# openSX70_ALPHA_V6-2-3-20181104.net
KiCad netlist of a schematic drawn in EAGLE
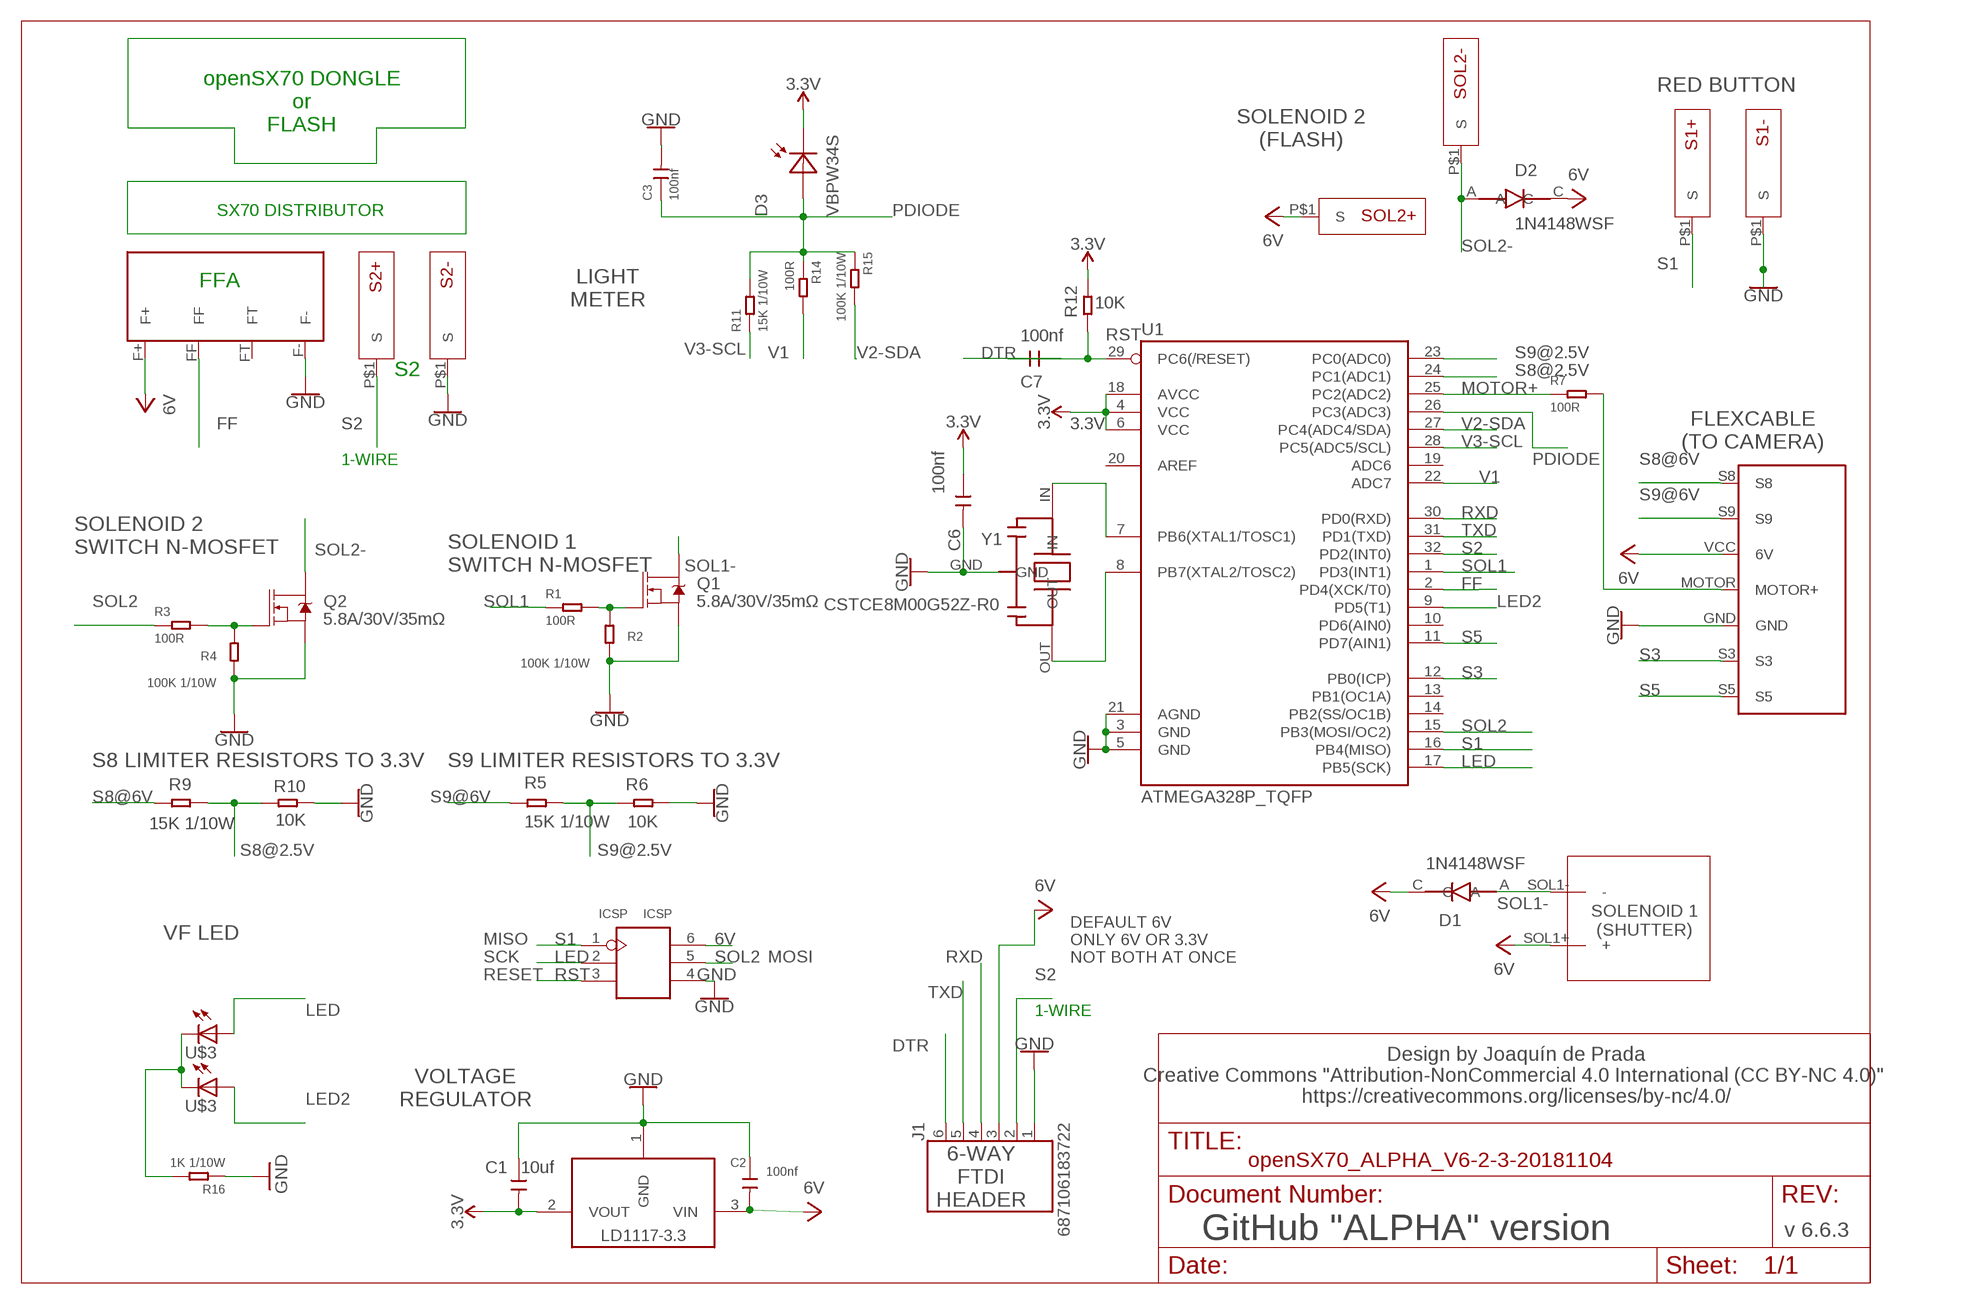
[diagram p0: schematic, sheet 1]

(export (version "E")
  (design (tool "Eeschema 10.0.6"))
  (components
    (comp (ref "C1")
      (value "10uf")
      (footprint "eagle-import:C0603")
      (fields (field (name "MPN") "CC0603KRX5R6BB106"))
      (libsource (lib "eagle-import") (part "CERAMIC-10UF-10V-10%-X5R(0603)"))
    )
    (comp (ref "C2")
      (value "100nf")
      (footprint "eagle-import:C0603")
      (fields (field (name "MPN") "CC0603KRX7R9BB104"))
      (libsource (lib "eagle-import") (part "CERAMIC-100NF-50V-10%-X7R(0603)"))
    )
    (comp (ref "C3")
      (value "100nf")
      (footprint "eagle-import:C0603")
      (fields (field (name "MPN") "CC0603KRX7R9BB104"))
      (libsource (lib "eagle-import") (part "CERAMIC-100NF-50V-10%-X7R(0603)"))
    )
    (comp (ref "C6")
      (value "100nf")
      (footprint "eagle-import:C0603")
      (fields (field (name "MPN") "CC0603KRX7R9BB104"))
      (libsource (lib "eagle-import") (part "CERAMIC-100NF-50V-10%-X7R(0603)"))
    )
    (comp (ref "C7")
      (value "100nf")
      (footprint "eagle-import:C0603")
      (fields (field (name "MPN") "CC0603KRX7R9BB104"))
      (libsource (lib "eagle-import") (part "CERAMIC-100NF-50V-10%-X7R(0603)"))
    )
    (comp (ref "D1")
      (value "1N4148WSF")
      (footprint "eagle-import:SODFL2512X100N")
      (fields (field (name "MANUFACTURER") "Fairchild Semiconductor"))
      (libsource (lib "eagle-import") (part "1N4148WS"))
    )
    (comp (ref "D2")
      (value "1N4148WSF")
      (footprint "eagle-import:SODFL2512X100N")
      (fields (field (name "MANUFACTURER") "Fairchild Semiconductor"))
      (libsource (lib "eagle-import") (part "1N4148WS"))
    )
    (comp (ref "D3")
      (value "VBPW34S")
      (footprint "eagle-import:SOD6439X130N")
      (fields (field (name "DIGI-KEY_PART_NUMBER") "751-1500-1-ND") (field (name "MF") "Vishay"))
      (libsource (lib "eagle-import") (part "VBPW34S"))
    )
    (comp (ref "ICSP")
      (value "ICSP")
      (footprint "eagle-import:H2X3-2.54")
      (libsource (lib "eagle-import") (part "ICSP"))
    )
    (comp (ref "J1")
      (value "687106183722")
      (footprint "eagle-import:687106183722")
      (fields (field (name "MF") "Wurth Electronics"))
      (libsource (lib "eagle-import") (part "687106183722"))
    )
    (comp (ref "LD11172.5V")
      (value "LD1117 2.5V")
      (footprint "eagle-import:SOT223")
      (fields (field (name "MF") "Advanced Monolithic Systems") (field (name "MP") "AMS1117-5.0"))
      (libsource (lib "eagle-import") (part "LD1117-3.3"))
    )
    (comp (ref "Q1")
      (value "5.8A/30V/35mΩ")
      (footprint "eagle-import:SOT23-3")
      (libsource (lib "eagle-import") (part "MOSFET-NCH-AO3404A"))
    )
    (comp (ref "Q2")
      (value "5.8A/30V/35mΩ")
      (footprint "eagle-import:SOT23-3")
      (libsource (lib "eagle-import") (part "MOSFET-NCH-AO3404A"))
    )
    (comp (ref "R1")
      (value "100R")
      (footprint "eagle-import:R0603")
      (fields (field (name "MPN") "RC0603JR-07100RL"))
      (libsource (lib "eagle-import") (part "SMD-RES-100R-5%-1/10W(0603)"))
    )
    (comp (ref "R2")
      (value "100K 1/10W")
      (footprint "eagle-import:R0603")
      (fields (field (name "MPN") "RC0603JR-07100KL"))
      (libsource (lib "eagle-import") (part "SMD-RES-100K-5%-1/10W(0603)"))
    )
    (comp (ref "R3")
      (value "100R")
      (footprint "eagle-import:R0603")
      (fields (field (name "MPN") "RC0603JR-07100RL"))
      (libsource (lib "eagle-import") (part "SMD-RES-100R-5%-1/10W(0603)"))
    )
    (comp (ref "R4")
      (value "100K 1/10W")
      (footprint "eagle-import:R0603")
      (fields (field (name "MPN") "RC0603JR-07100KL"))
      (libsource (lib "eagle-import") (part "SMD-RES-100K-5%-1/10W(0603)"))
    )
    (comp (ref "R5")
      (value "15K 1/10W")
      (footprint "eagle-import:R0603")
      (fields (field (name "MPN") "RC0603FR-0715KL"))
      (libsource (lib "eagle-import") (part "SMD-RES-15K-1%-1/10W(0603)"))
    )
    (comp (ref "R6")
      (value "10K")
      (footprint "eagle-import:R0603")
      (fields (field (name "MPN") "RC0603FR-0710KL"))
      (libsource (lib "eagle-import") (part "SMD-RES-10K-1%-1/10W(0603)"))
    )
    (comp (ref "R7")
      (value "100R")
      (footprint "eagle-import:R0603")
      (fields (field (name "MPN") "RC0603JR-07100RL"))
      (libsource (lib "eagle-import") (part "SMD-RES-100R-5%-1/10W(0603)"))
    )
    (comp (ref "R9")
      (value "15K 1/10W")
      (footprint "eagle-import:R0603")
      (fields (field (name "MPN") "RC0603FR-0715KL"))
      (libsource (lib "eagle-import") (part "SMD-RES-15K-1%-1/10W(0603)"))
    )
    (comp (ref "R10")
      (value "10K")
      (footprint "eagle-import:R0603")
      (fields (field (name "MPN") "RC0603FR-0710KL"))
      (libsource (lib "eagle-import") (part "SMD-RES-10K-1%-1/10W(0603)"))
    )
    (comp (ref "R11")
      (value "15K 1/10W")
      (footprint "eagle-import:R0603")
      (fields (field (name "MPN") "RC0603FR-0715KL"))
      (libsource (lib "eagle-import") (part "SMD-RES-15K-1%-1/10W(0603)"))
    )
    (comp (ref "R12")
      (value "10K")
      (footprint "eagle-import:R0603")
      (fields (field (name "MPN") "RC0603FR-0710KL"))
      (libsource (lib "eagle-import") (part "SMD-RES-10K-1%-1/10W(0603)"))
    )
    (comp (ref "R14")
      (value "100R")
      (footprint "eagle-import:R0603")
      (fields (field (name "MPN") "RC0603JR-07100RL"))
      (libsource (lib "eagle-import") (part "SMD-RES-100R-5%-1/10W(0603)"))
    )
    (comp (ref "R15")
      (value "100K 1/10W")
      (footprint "eagle-import:R0603")
      (fields (field (name "MPN") "RC0603JR-07100KL"))
      (libsource (lib "eagle-import") (part "SMD-RES-100K-5%-1/10W(0603)"))
    )
    (comp (ref "R16")
      (value "1K 1/10W")
      (footprint "eagle-import:R0603")
      (fields (field (name "MPN") "RC0603JR-071KL"))
      (libsource (lib "eagle-import") (part "SMD-RES-1K-5%-1/10W(0603)"))
    )
    (comp (ref "S1+")
      (value "SX70-S-PAD-NEW")
      (footprint "eagle-import:SX70-S-PAD2")
      (libsource (lib "eagle-import") (part "SX70-S-PAD-NEW"))
    )
    (comp (ref "S1-")
      (value "SX70-S-PAD-NEW")
      (footprint "eagle-import:SX70-S-PAD2")
      (libsource (lib "eagle-import") (part "SX70-S-PAD-NEW"))
    )
    (comp (ref "S2+")
      (value "SX70-S-PAD-NEW")
      (footprint "eagle-import:SX70-S-PAD2")
      (libsource (lib "eagle-import") (part "SX70-S-PAD-NEW"))
    )
    (comp (ref "S2-")
      (value "SX70-S-PAD-NEW")
      (footprint "eagle-import:SX70-S-PAD2")
      (libsource (lib "eagle-import") (part "SX70-S-PAD-NEW"))
    )
    (comp (ref "SOL1")
      (value "SX70-SOLENOID1-2PADS")
      (footprint "eagle-import:SX70-SOLENOID1-2")
      (libsource (lib "eagle-import") (part "SX70-SOLENOID1-2PADS"))
    )
    (comp (ref "SOL2+")
      (value "SX70-S-PAD-NEW")
      (footprint "eagle-import:SX70-S-PAD2")
      (libsource (lib "eagle-import") (part "SX70-S-PAD-NEW"))
    )
    (comp (ref "SOL2-")
      (value "SX70-S-PAD-NEW")
      (footprint "eagle-import:SX70-S-PAD2")
      (libsource (lib "eagle-import") (part "SX70-S-PAD-NEW"))
    )
    (comp (ref "U$1")
      (value "SX70-7-PAD")
      (footprint "eagle-import:SX70-7-PAD-PROPER")
      (libsource (lib "eagle-import") (part "SX70-7-PAD"))
    )
    (comp (ref "U$2")
      (value "FFA")
      (footprint "eagle-import:FFA-PAD-PACKAGE")
      (libsource (lib "eagle-import") (part "SX70-FFA-PAD"))
    )
    (comp (ref "U$3")
      (value "DUAL-LED-0603-BIS")
      (footprint "eagle-import:LED_APHB1608SYKSURKC")
      (libsource (lib "eagle-import") (part "DUAL-LED-0603-BIS"))
    )
    (comp (ref "U1")
      (value "ATMEGA328P_TQFP")
      (footprint "eagle-import:TQFP32-08")
      (libsource (lib "eagle-import") (part "ATMEGA328P_TQFP"))
    )
    (comp (ref "Y1")
      (value "CSTCE8M00G52Z-R0")
      (footprint "eagle-import:CFP95P160X100-3N")
      (fields (field (name "MF") "Murata") (field (name "MP") "CSTCE16M0V53-R0"))
      (libsource (lib "eagle-import") (part "CSTCE16M0V53-R0"))
    )
  )
  (nets
    (net (code "1") (name "/DTR") (class "Default")
      (node (ref "C7") (pin "1") (pinfunction "1_1") (pintype "passive"))
      (node (ref "J1") (pin "6") (pinfunction "1_6") (pintype "passive"))
    )
    (net (code "2") (name "/FF") (class "Default")
      (node (ref "U$2") (pin "FF") (pinfunction "FF_FF") (pintype "bidirectional"))
      (node (ref "U1") (pin "2") (pinfunction "PD4(XCK/T0)_2") (pintype "bidirectional"))
    )
    (net (code "3") (name "/LED") (class "Default")
      (node (ref "ICSP") (pin "2") (pinfunction "SCK_2") (pintype "bidirectional"))
      (node (ref "U$3") (pin "1") (pinfunction "A_1") (pintype "passive"))
      (node (ref "U1") (pin "17") (pinfunction "PB5(SCK)_17") (pintype "bidirectional"))
    )
    (net (code "4") (name "/LED2") (class "Default")
      (node (ref "U$3") (pin "3") (pinfunction "A1_3") (pintype "passive"))
      (node (ref "U1") (pin "9") (pinfunction "PD5(T1)_9") (pintype "bidirectional"))
    )
    (net (code "5") (name "/MOTOR+") (class "Default")
      (node (ref "R7") (pin "1") (pinfunction "1_1") (pintype "passive"))
      (node (ref "U1") (pin "25") (pinfunction "PC2(ADC2)_25") (pintype "bidirectional"))
    )
    (net (code "6") (name "/PDIODE") (class "Default")
      (node (ref "C3") (pin "1") (pinfunction "1_1") (pintype "passive"))
      (node (ref "D3") (pin "A") (pinfunction "A_A") (pintype "passive"))
      (node (ref "R11") (pin "2") (pinfunction "2_2") (pintype "passive"))
      (node (ref "R14") (pin "1") (pinfunction "1_1") (pintype "passive"))
      (node (ref "R15") (pin "1") (pinfunction "1_1") (pintype "passive"))
      (node (ref "U1") (pin "26") (pinfunction "PC3(ADC3)_26") (pintype "bidirectional"))
    )
    (net (code "7") (name "/RST") (class "Default")
      (node (ref "C7") (pin "2") (pinfunction "2_2") (pintype "passive"))
      (node (ref "ICSP") (pin "3") (pinfunction "RST_3") (pintype "bidirectional"))
      (node (ref "R12") (pin "1") (pinfunction "1_1") (pintype "passive"))
      (node (ref "U1") (pin "29") (pinfunction "PC6(/RESET)_29") (pintype "bidirectional"))
    )
    (net (code "8") (name "/RXD") (class "Default")
      (node (ref "J1") (pin "4") (pinfunction "3_4") (pintype "passive"))
      (node (ref "U1") (pin "30") (pinfunction "PD0(RXD)_30") (pintype "bidirectional"))
    )
    (net (code "9") (name "/S1") (class "Default")
      (node (ref "ICSP") (pin "1") (pinfunction "MISO_1") (pintype "bidirectional"))
      (node (ref "S1+") (pin "P$1") (pinfunction "S_P$1") (pintype "bidirectional"))
      (node (ref "U1") (pin "16") (pinfunction "PB4(MISO)_16") (pintype "bidirectional"))
    )
    (net (code "10") (name "/S2") (class "Default")
      (node (ref "J1") (pin "2") (pinfunction "5_2") (pintype "passive"))
      (node (ref "S2+") (pin "P$1") (pinfunction "S_P$1") (pintype "bidirectional"))
      (node (ref "U1") (pin "32") (pinfunction "PD2(INT0)_32") (pintype "bidirectional"))
    )
    (net (code "11") (name "/S3") (class "Default")
      (node (ref "U$1") (pin "S3") (pinfunction "S3_S3") (pintype "bidirectional"))
      (node (ref "U1") (pin "12") (pinfunction "PB0(ICP)_12") (pintype "bidirectional"))
    )
    (net (code "12") (name "/S5") (class "Default")
      (node (ref "U$1") (pin "S5") (pinfunction "S5_S5") (pintype "bidirectional"))
      (node (ref "U1") (pin "11") (pinfunction "PD7(AIN1)_11") (pintype "bidirectional"))
    )
    (net (code "13") (name "/S8@2.5V") (class "Default")
      (node (ref "R10") (pin "1") (pinfunction "1_1") (pintype "passive"))
      (node (ref "R9") (pin "2") (pinfunction "2_2") (pintype "passive"))
      (node (ref "U1") (pin "24") (pinfunction "PC1(ADC1)_24") (pintype "bidirectional"))
    )
    (net (code "14") (name "/S8@6V") (class "Default")
      (node (ref "R9") (pin "1") (pinfunction "1_1") (pintype "passive"))
      (node (ref "U$1") (pin "S8") (pinfunction "S8_S8") (pintype "bidirectional"))
    )
    (net (code "15") (name "/S9@2.5V") (class "Default")
      (node (ref "R5") (pin "2") (pinfunction "2_2") (pintype "passive"))
      (node (ref "R6") (pin "1") (pinfunction "1_1") (pintype "passive"))
      (node (ref "U1") (pin "23") (pinfunction "PC0(ADC0)_23") (pintype "bidirectional"))
    )
    (net (code "16") (name "/S9@6V") (class "Default")
      (node (ref "R5") (pin "1") (pinfunction "1_1") (pintype "passive"))
      (node (ref "U$1") (pin "S9") (pinfunction "S9_S9") (pintype "bidirectional"))
    )
    (net (code "17") (name "/SOL1") (class "Default")
      (node (ref "R1") (pin "1") (pinfunction "1_1") (pintype "passive"))
      (node (ref "U1") (pin "1") (pinfunction "PD3(INT1)_1") (pintype "bidirectional"))
    )
    (net (code "18") (name "/SOL1-") (class "Default")
      (node (ref "D1") (pin "A") (pinfunction "A_A") (pintype "passive"))
      (node (ref "Q1") (pin "3") (pinfunction "D_3") (pintype "bidirectional"))
      (node (ref "SOL1") (pin "SOL1-") (pinfunction "-_SOL1-") (pintype "bidirectional"))
    )
    (net (code "19") (name "/SOL2") (class "Default")
      (node (ref "ICSP") (pin "5") (pinfunction "MOSI_5") (pintype "bidirectional"))
      (node (ref "R3") (pin "1") (pinfunction "1_1") (pintype "passive"))
      (node (ref "U1") (pin "15") (pinfunction "PB3(MOSI/OC2)_15") (pintype "bidirectional"))
    )
    (net (code "20") (name "/SOL2-") (class "Default")
      (node (ref "D2") (pin "A") (pinfunction "A_A") (pintype "passive"))
      (node (ref "Q2") (pin "3") (pinfunction "D_3") (pintype "bidirectional"))
      (node (ref "SOL2-") (pin "P$1") (pinfunction "S_P$1") (pintype "bidirectional"))
    )
    (net (code "21") (name "/TXD") (class "Default")
      (node (ref "J1") (pin "5") (pinfunction "2_5") (pintype "passive"))
      (node (ref "U1") (pin "31") (pinfunction "PD1(TXD)_31") (pintype "bidirectional"))
    )
    (net (code "22") (name "/V1") (class "Default")
      (node (ref "R14") (pin "2") (pinfunction "2_2") (pintype "passive"))
      (node (ref "U1") (pin "22") (pinfunction "ADC7_22") (pintype "bidirectional"))
    )
    (net (code "23") (name "/V2-SDA") (class "Default")
      (node (ref "R15") (pin "2") (pinfunction "2_2") (pintype "passive"))
      (node (ref "U1") (pin "27") (pinfunction "PC4(ADC4/SDA)_27") (pintype "bidirectional"))
    )
    (net (code "24") (name "/V3-SCL") (class "Default")
      (node (ref "R11") (pin "1") (pinfunction "1_1") (pintype "passive"))
      (node (ref "U1") (pin "28") (pinfunction "PC5(ADC5/SCL)_28") (pintype "bidirectional"))
    )
    (net (code "25") (name "3.3V") (class "Default")
      (node (ref "C1") (pin "2") (pinfunction "2_2") (pintype "passive"))
      (node (ref "C6") (pin "1") (pinfunction "1_1") (pintype "passive"))
      (node (ref "D3") (pin "C") (pinfunction "C_C") (pintype "passive"))
      (node (ref "LD11172.5V") (pin "2") (pinfunction "VOUT_2") (pintype "bidirectional"))
      (node (ref "R12") (pin "2") (pinfunction "2_2") (pintype "passive"))
      (node (ref "U1") (pin "18") (pinfunction "AVCC_18") (pintype "bidirectional"))
      (node (ref "U1") (pin "4") (pinfunction "VCC_4") (pintype "bidirectional"))
      (node (ref "U1") (pin "6") (pinfunction "VCC_6") (pintype "bidirectional"))
    )
    (net (code "26") (name "6V") (class "Default")
      (node (ref "C2") (pin "2") (pinfunction "2_2") (pintype "passive"))
      (node (ref "D1") (pin "C") (pinfunction "C_C") (pintype "passive"))
      (node (ref "D2") (pin "C") (pinfunction "C_C") (pintype "passive"))
      (node (ref "ICSP") (pin "6") (pinfunction "VCC_6") (pintype "bidirectional"))
      (node (ref "J1") (pin "3") (pinfunction "4_3") (pintype "passive"))
      (node (ref "LD11172.5V") (pin "3") (pinfunction "VIN_3") (pintype "bidirectional"))
      (node (ref "SOL1") (pin "SOL1+") (pinfunction "+_SOL1+") (pintype "bidirectional"))
      (node (ref "SOL2+") (pin "P$1") (pinfunction "S_P$1") (pintype "bidirectional"))
      (node (ref "U$1") (pin "VCC") (pinfunction "6V_VCC") (pintype "bidirectional"))
      (node (ref "U$2") (pin "F+") (pinfunction "F+_F+") (pintype "bidirectional"))
    )
    (net (code "27") (name "GND") (class "Default")
      (node (ref "C1") (pin "1") (pinfunction "1_1") (pintype "passive"))
      (node (ref "C2") (pin "1") (pinfunction "1_1") (pintype "passive"))
      (node (ref "C3") (pin "2") (pinfunction "2_2") (pintype "passive"))
      (node (ref "C6") (pin "2") (pinfunction "2_2") (pintype "passive"))
      (node (ref "ICSP") (pin "4") (pinfunction "GND_4") (pintype "bidirectional"))
      (node (ref "J1") (pin "1") (pinfunction "6_1") (pintype "passive"))
      (node (ref "LD11172.5V") (pin "1") (pinfunction "GND_1") (pintype "bidirectional"))
      (node (ref "Q1") (pin "2") (pinfunction "S_2") (pintype "bidirectional"))
      (node (ref "Q2") (pin "2") (pinfunction "S_2") (pintype "bidirectional"))
      (node (ref "R10") (pin "2") (pinfunction "2_2") (pintype "passive"))
      (node (ref "R16") (pin "1") (pinfunction "1_1") (pintype "passive"))
      (node (ref "R2") (pin "1") (pinfunction "1_1") (pintype "passive"))
      (node (ref "R4") (pin "1") (pinfunction "1_1") (pintype "passive"))
      (node (ref "R6") (pin "2") (pinfunction "2_2") (pintype "passive"))
      (node (ref "S1-") (pin "P$1") (pinfunction "S_P$1") (pintype "bidirectional"))
      (node (ref "S2-") (pin "P$1") (pinfunction "S_P$1") (pintype "bidirectional"))
      (node (ref "U$1") (pin "GND") (pinfunction "GND_GND") (pintype "bidirectional"))
      (node (ref "U$2") (pin "F-") (pinfunction "F-_F-") (pintype "bidirectional"))
      (node (ref "U1") (pin "21") (pinfunction "AGND_21") (pintype "bidirectional"))
      (node (ref "U1") (pin "3") (pinfunction "GND_3") (pintype "bidirectional"))
      (node (ref "U1") (pin "5") (pinfunction "GND_5") (pintype "bidirectional"))
      (node (ref "Y1") (pin "GND") (pinfunction "GND_GND") (pintype "passive"))
    )
    (net (code "28") (name "Net-(Q1-G)") (class "Default")
      (node (ref "Q1") (pin "1") (pinfunction "G_1") (pintype "bidirectional"))
      (node (ref "R1") (pin "2") (pinfunction "2_2") (pintype "passive"))
      (node (ref "R2") (pin "2") (pinfunction "2_2") (pintype "passive"))
    )
    (net (code "29") (name "Net-(Q2-G)") (class "Default")
      (node (ref "Q2") (pin "1") (pinfunction "G_1") (pintype "bidirectional"))
      (node (ref "R3") (pin "2") (pinfunction "2_2") (pintype "passive"))
      (node (ref "R4") (pin "2") (pinfunction "2_2") (pintype "passive"))
    )
    (net (code "30") (name "Net-(U$1-MOTOR+)") (class "Default")
      (node (ref "R7") (pin "2") (pinfunction "2_2") (pintype "passive"))
      (node (ref "U$1") (pin "MOTOR") (pinfunction "MOTOR+_MOTOR") (pintype "bidirectional"))
    )
    (net (code "31") (name "Net-(U$3-C)") (class "Default")
      (node (ref "R16") (pin "2") (pinfunction "2_2") (pintype "passive"))
      (node (ref "U$3") (pin "2") (pinfunction "C_2") (pintype "passive"))
      (node (ref "U$3") (pin "4") (pinfunction "C1_4") (pintype "passive"))
    )
    (net (code "32") (name "Net-(U1-PB6(XTAL1{slash}TOSC1))") (class "Default")
      (node (ref "U1") (pin "7") (pinfunction "PB6(XTAL1/TOSC1)_7") (pintype "bidirectional"))
      (node (ref "Y1") (pin "IN") (pinfunction "IN_IN") (pintype "input"))
    )
    (net (code "33") (name "Net-(U1-PB7(XTAL2{slash}TOSC2))") (class "Default")
      (node (ref "U1") (pin "8") (pinfunction "PB7(XTAL2/TOSC2)_8") (pintype "bidirectional"))
      (node (ref "Y1") (pin "OUT") (pinfunction "OUT_OUT") (pintype "output"))
    )
    (net (code "34") (name "unconnected-(U$2-PadFT)") (class "Default")
      (node (ref "U$2") (pin "FT") (pinfunction "FT_FT") (pintype "bidirectional"))
    )
    (net (code "35") (name "unconnected-(U1-ADC6-Pad19)") (class "Default")
      (node (ref "U1") (pin "19") (pinfunction "ADC6_19") (pintype "bidirectional"))
    )
    (net (code "36") (name "unconnected-(U1-AREF-Pad20)") (class "Default")
      (node (ref "U1") (pin "20") (pinfunction "AREF_20") (pintype "bidirectional"))
    )
    (net (code "37") (name "unconnected-(U1-PB1(OC1A)-Pad13)") (class "Default")
      (node (ref "U1") (pin "13") (pinfunction "PB1(OC1A)_13") (pintype "bidirectional"))
    )
    (net (code "38") (name "unconnected-(U1-PB2(SS{slash}OC1B)-Pad14)") (class "Default")
      (node (ref "U1") (pin "14") (pinfunction "PB2(SS/OC1B)_14") (pintype "bidirectional"))
    )
    (net (code "39") (name "unconnected-(U1-PD6(AIN0)-Pad10)") (class "Default")
      (node (ref "U1") (pin "10") (pinfunction "PD6(AIN0)_10") (pintype "bidirectional"))
    )
  )
)
